# Edzzanine_Base.net
KiCad netlist of a schematic drawn in EAGLE
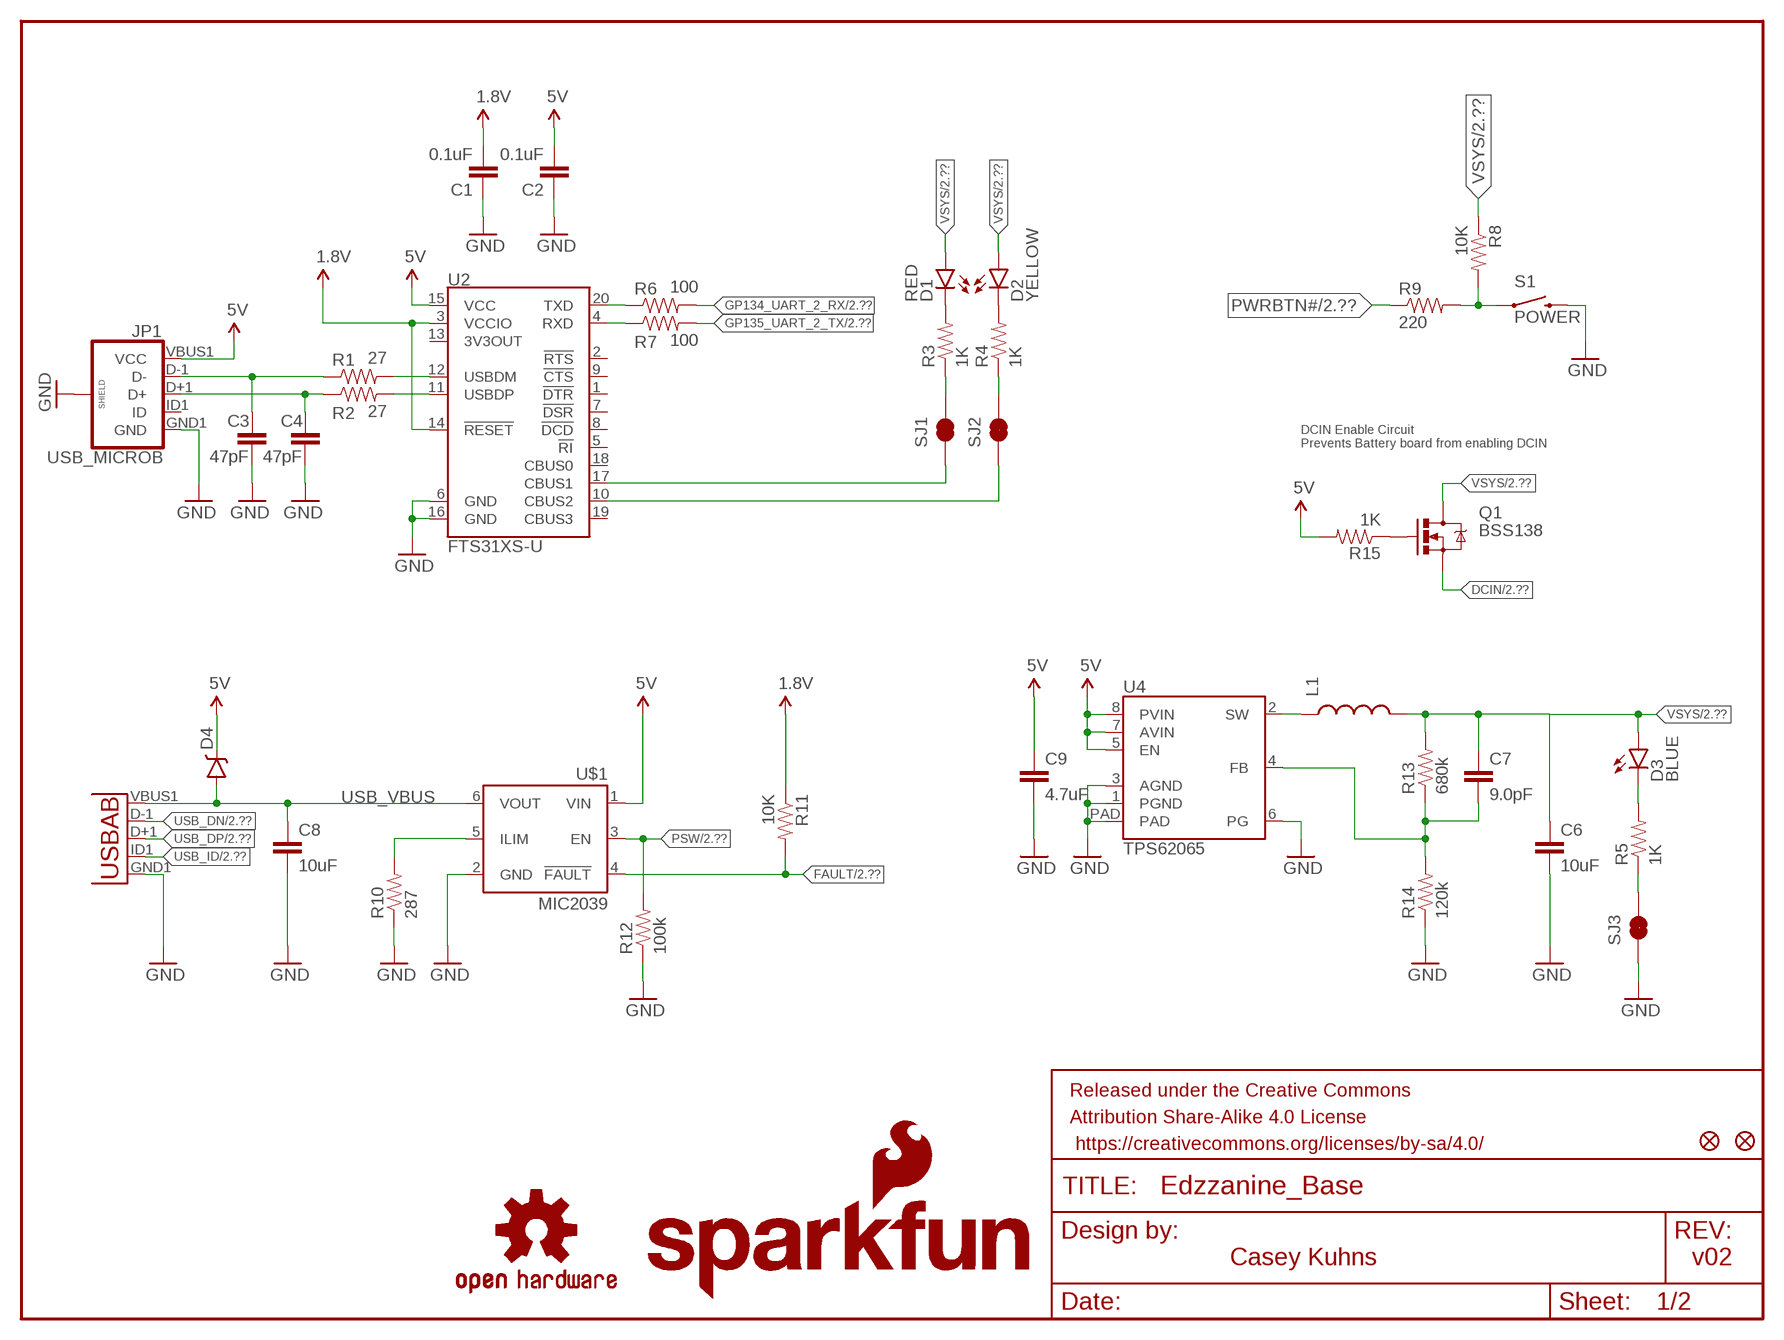
[diagram p0: schematic, sheet 1]
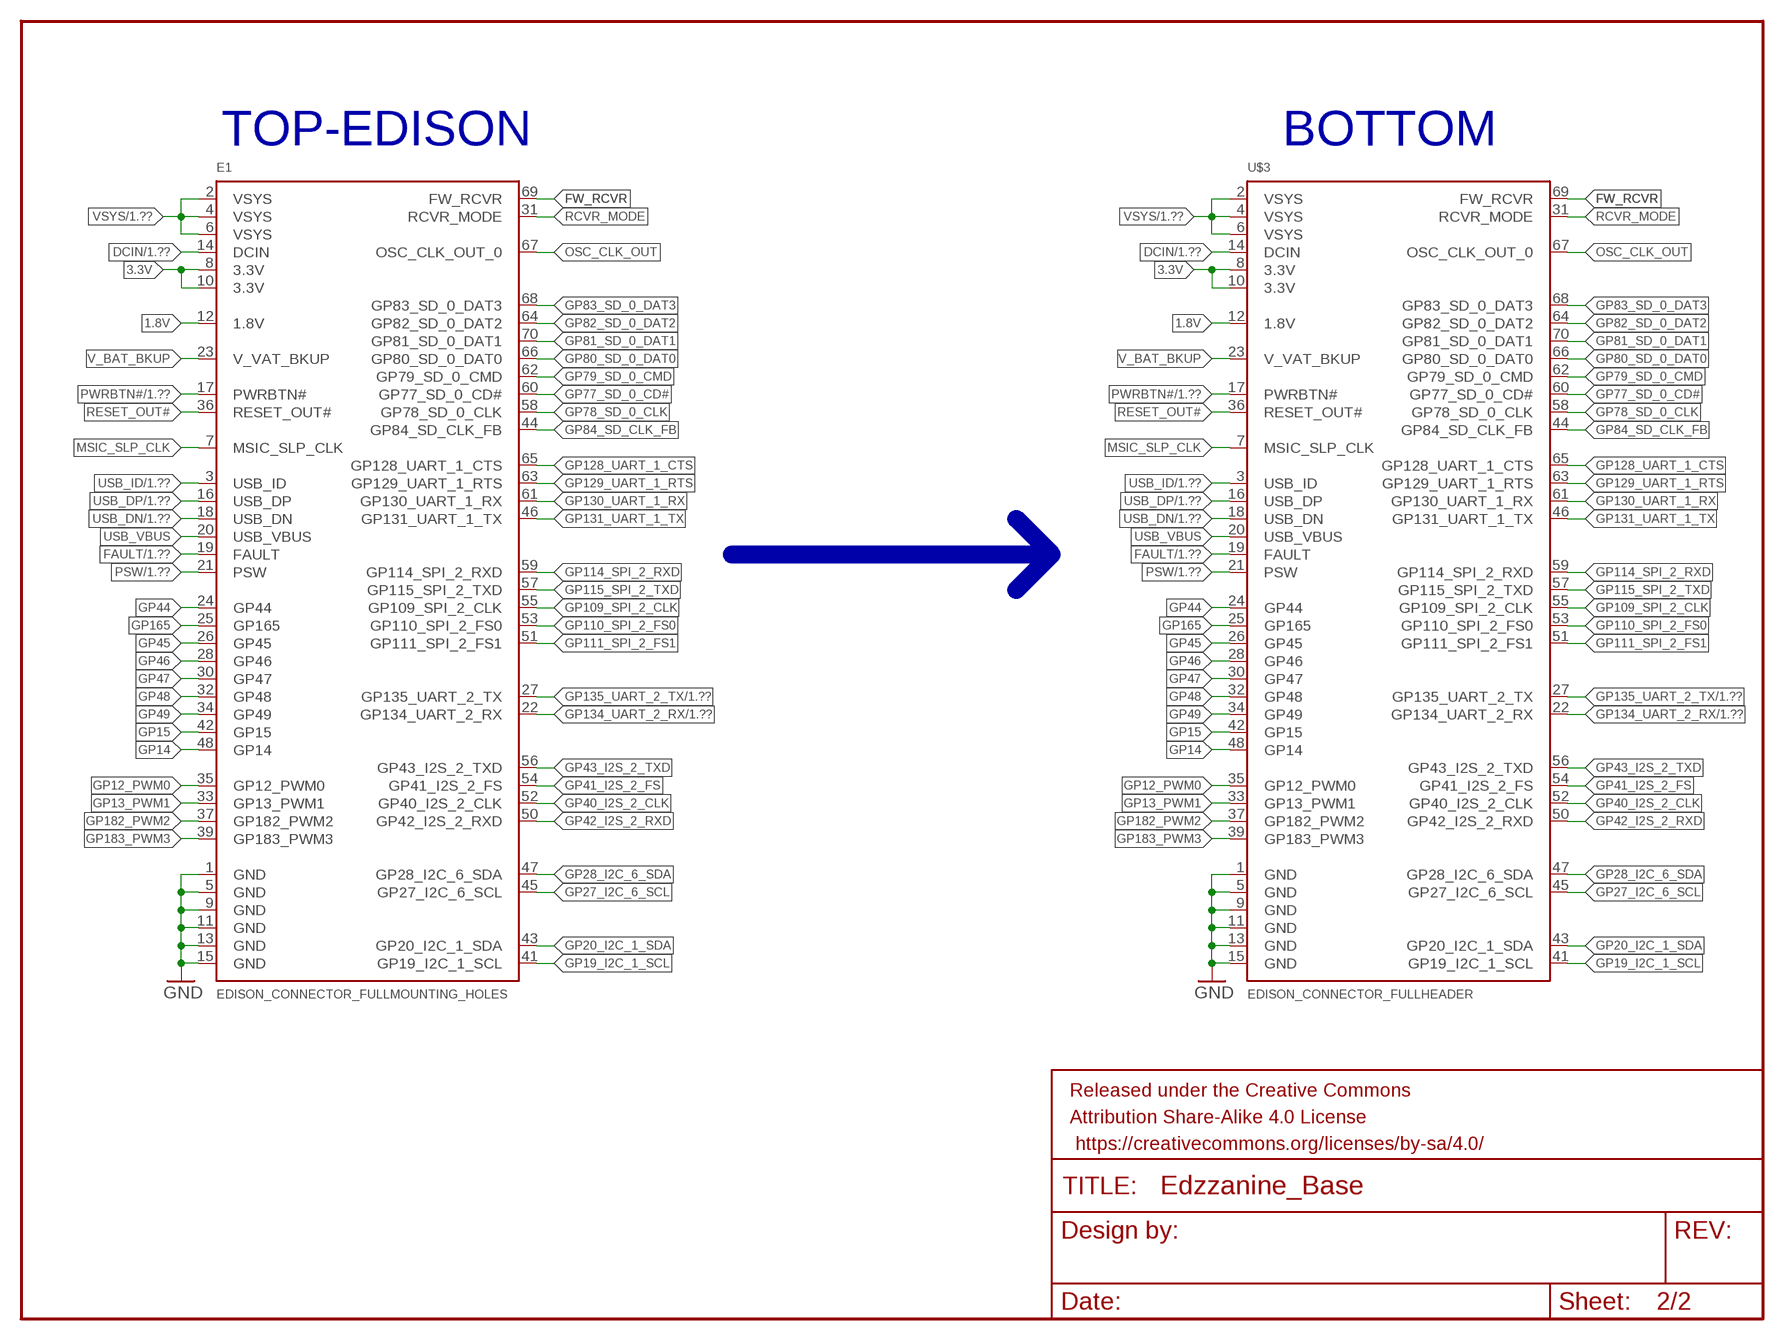
[diagram p1: schematic, sheet 2]

(export (version "E")
  (design (tool "Eeschema 10.0.6"))
  (components
    (comp (ref "C1")
      (value "0.1uF")
      (footprint "eagle-import:0603-CAP")
      (libsource (lib "eagle-import") (part "0.1UF-25V(+80/-20%)(0603)"))
    )
    (comp (ref "C2")
      (value "0.1uF")
      (footprint "eagle-import:0603-CAP")
      (libsource (lib "eagle-import") (part "0.1UF-25V(+80/-20%)(0603)"))
    )
    (comp (ref "C3")
      (value "47pF")
      (footprint "eagle-import:0603-CAP")
      (libsource (lib "eagle-import") (part "47PF-50V-5%(0603)"))
    )
    (comp (ref "C4")
      (value "47pF")
      (footprint "eagle-import:0603-CAP")
      (libsource (lib "eagle-import") (part "47PF-50V-5%(0603)"))
    )
    (comp (ref "C6")
      (value "10uF")
      (footprint "eagle-import:1206")
      (libsource (lib "eagle-import") (part "10UF-6.3V-20%(1206)"))
    )
    (comp (ref "C7")
      (value "9.0pF")
      (footprint "eagle-import:0603-CAP")
      (libsource (lib "eagle-import") (part "9.0PF-50V-10%(0603)"))
    )
    (comp (ref "C8")
      (value "10uF")
      (footprint "eagle-import:1206")
      (libsource (lib "eagle-import") (part "10UF-6.3V-20%(1206)"))
    )
    (comp (ref "C9")
      (value "4.7uF")
      (footprint "eagle-import:0603-CAP")
      (libsource (lib "eagle-import") (part "4.7UF-6.3V-10%(0603)0603"))
    )
    (comp (ref "D1")
      (value "RED")
      (footprint "eagle-import:LED-0603")
      (libsource (lib "eagle-import") (part "LED-RED0603"))
    )
    (comp (ref "D2")
      (value "YELLOW")
      (footprint "eagle-import:LED-0603")
      (libsource (lib "eagle-import") (part "LED-YELLOW0603"))
    )
    (comp (ref "D3")
      (value "BLUE")
      (footprint "eagle-import:LED-0603")
      (libsource (lib "eagle-import") (part "LED-BLUE0603"))
    )
    (comp (ref "D4")
      (value "DIODE-SCHOTTKY-MBRA140")
      (footprint "eagle-import:SMA-DIODE")
      (libsource (lib "eagle-import") (part "DIODE-SCHOTTKY-MBRA140"))
    )
    (comp (ref "FID1")
      (value "FIDUCIAL1X2")
      (footprint "eagle-import:FIDUCIAL-1X2")
      (libsource (lib "eagle-import") (part "FIDUCIAL1X2"))
    )
    (comp (ref "FID2")
      (value "FIDUCIAL1X2")
      (footprint "eagle-import:FIDUCIAL-1X2")
      (libsource (lib "eagle-import") (part "FIDUCIAL1X2"))
    )
    (comp (ref "FRAME1")
      (value "FRAME-LETTER")
      (footprint "eagle-import:CREATIVE_COMMONS")
      (libsource (lib "eagle-import") (part "FRAME-LETTER"))
    )
    (comp (ref "JP1")
      (value "USB_MICROB")
      (footprint "eagle-import:USB-B-MICRO-SMD_V03")
      (libsource (lib "eagle-import") (part "USB_MICROB_PLUGCONN-11752"))
    )
    (comp (ref "L1")
      (value "INDUCTOR")
      (footprint "eagle-import:INDUCTOR-SRP4020")
      (libsource (lib "eagle-import") (part "INDUCTOR"))
    )
    (comp (ref "LOGO1")
      (value "SFE_LOGO_NAME_FLAME.1_INCH")
      (footprint "eagle-import:SFE_LOGO_NAME_FLAME_.1")
      (libsource (lib "eagle-import") (part "SFE_LOGO_NAME_FLAME.1_INCH"))
    )
    (comp (ref "LOGO4")
      (value "OSHW-LOGOS")
      (footprint "eagle-import:OSHW-LOGO-S")
      (libsource (lib "eagle-import") (part "OSHW-LOGOS"))
    )
    (comp (ref "Q1")
      (value "BSS138")
      (footprint "eagle-import:SOT23-3")
      (libsource (lib "eagle-import") (part "MOSFET-NCHANNELBSS138"))
    )
    (comp (ref "R1")
      (value "27")
      (footprint "eagle-import:0603")
      (libsource (lib "eagle-import") (part "27OHM1/10W1%(0603)"))
    )
    (comp (ref "R2")
      (value "27")
      (footprint "eagle-import:0603")
      (libsource (lib "eagle-import") (part "27OHM1/10W1%(0603)"))
    )
    (comp (ref "R3")
      (value "1K")
      (footprint "eagle-import:0603-RES")
      (libsource (lib "eagle-import") (part "1KOHM1/10W1%(0603)"))
    )
    (comp (ref "R4")
      (value "1K")
      (footprint "eagle-import:0603-RES")
      (libsource (lib "eagle-import") (part "1KOHM1/10W1%(0603)"))
    )
    (comp (ref "R5")
      (value "1K")
      (footprint "eagle-import:0603-RES")
      (libsource (lib "eagle-import") (part "1KOHM1/10W1%(0603)"))
    )
    (comp (ref "R6")
      (value "100")
      (footprint "eagle-import:0603-RES")
      (libsource (lib "eagle-import") (part "100OHM1/10W1%(0603)"))
    )
    (comp (ref "R7")
      (value "100")
      (footprint "eagle-import:0603-RES")
      (libsource (lib "eagle-import") (part "100OHM1/10W1%(0603)"))
    )
    (comp (ref "R8")
      (value "10K")
      (footprint "eagle-import:0603-RES")
      (libsource (lib "eagle-import") (part "10KOHM1/10W1%(0603)0603"))
    )
    (comp (ref "R9")
      (value "220")
      (footprint "eagle-import:0603-RES")
      (libsource (lib "eagle-import") (part "22OHM1/10W1%(0603)"))
    )
    (comp (ref "R10")
      (value "287")
      (footprint "eagle-import:0603-RES")
      (libsource (lib "eagle-import") (part "287OHM-1/10W-1%(0603)"))
    )
    (comp (ref "R11")
      (value "10K")
      (footprint "eagle-import:0603-RES")
      (libsource (lib "eagle-import") (part "10KOHM1/10W1%(0603)0603"))
    )
    (comp (ref "R12")
      (value "100k")
      (footprint "eagle-import:0603-RES")
      (libsource (lib "eagle-import") (part "100KOHM1/10W1%(0603)"))
    )
    (comp (ref "R13")
      (value "680k")
      (footprint "eagle-import:0603-RES")
      (libsource (lib "eagle-import") (part "RESISTOR0603"))
    )
    (comp (ref "R14")
      (value "120k")
      (footprint "eagle-import:0603-RES")
      (libsource (lib "eagle-import") (part "RESISTOR0603"))
    )
    (comp (ref "R15")
      (value "1K")
      (footprint "eagle-import:0603-RES")
      (libsource (lib "eagle-import") (part "1KOHM1/10W1%(0603)"))
    )
    (comp (ref "S1")
      (value "POWER")
      (footprint "eagle-import:TACTILE_SWITCH-SMD-RIGHT-ANGLE")
      (libsource (lib "eagle-import") (part "SWITCH-MOMENTARY-2TACTILE-SWITCH-SMD-RIGHT-ANGLE"))
    )
    (comp (ref "SJ1")
      (value "JUMPER-PAD-2-NC_BY_TRACE")
      (footprint "eagle-import:PAD-JUMPER-2-NC_BY_TRACE_YES_SILK")
      (libsource (lib "eagle-import") (part "JUMPER-PAD-2-NC_BY_TRACE"))
    )
    (comp (ref "SJ2")
      (value "JUMPER-PAD-2-NC_BY_TRACE")
      (footprint "eagle-import:PAD-JUMPER-2-NC_BY_TRACE_YES_SILK")
      (libsource (lib "eagle-import") (part "JUMPER-PAD-2-NC_BY_TRACE"))
    )
    (comp (ref "SJ3")
      (value "JUMPER-PAD-2-NC_BY_TRACE")
      (footprint "eagle-import:PAD-JUMPER-2-NC_BY_TRACE_YES_SILK")
      (libsource (lib "eagle-import") (part "JUMPER-PAD-2-NC_BY_TRACE"))
    )
    (comp (ref "U$1")
      (value "MIC2039")
      (footprint "eagle-import:SOT23-6")
      (libsource (lib "eagle-import") (part "MIC2039"))
    )
    (comp (ref "U2")
      (value "FTS31XS-U")
      (footprint "eagle-import:SSOP20_L")
      (libsource (lib "eagle-import") (part "FT231XS"))
    )
    (comp (ref "U3")
      (value "USB-ABCONN-11794")
      (footprint "eagle-import:USB-AB-MICRO-SMD_V03")
      (libsource (lib "eagle-import") (part "USB-ABCONN-11794"))
    )
    (comp (ref "U4")
      (value "TPS62065")
      (footprint "eagle-import:WSON-8-PAD")
      (libsource (lib "eagle-import") (part "TPS62065"))
    )
    (comp (ref "E1")
      (value "EDISON_CONNECTOR_FULLMOUNTING_HOLES")
      (footprint "eagle-import:EDISON_DAUGHTER")
      (libsource (lib "eagle-import") (part "EDISON_CONNECTOR_FULLMOUNTING_HOLES"))
    )
    (comp (ref "FRAME2")
      (value "FRAME-LETTER")
      (footprint "eagle-import:CREATIVE_COMMONS")
      (libsource (lib "eagle-import") (part "FRAME-LETTER"))
    )
    (comp (ref "U$3")
      (value "EDISON_CONNECTOR_FULLHEADER")
      (footprint "eagle-import:DF40C-70DP-0.4(51)")
      (libsource (lib "eagle-import") (part "EDISON_CONNECTOR_FULLHEADER"))
    )
  )
  (nets
    (net (code "1") (name "1.8V") (class "Default")
      (node (ref "C1") (pin "2") (pinfunction "2_2") (pintype "passive"))
      (node (ref "E1") (pin "12") (pinfunction "1.8V_12") (pintype "bidirectional"))
      (node (ref "R11") (pin "1") (pinfunction "1_1") (pintype "passive"))
      (node (ref "U$3") (pin "12") (pinfunction "1.8V_12") (pintype "bidirectional"))
      (node (ref "U2") (pin "14") (pinfunction "~{RESET}_14") (pintype "bidirectional"))
      (node (ref "U2") (pin "3") (pinfunction "VCCIO_3") (pintype "bidirectional"))
    )
    (net (code "2") (name "3.3V") (class "Default")
      (node (ref "E1") (pin "10") (pinfunction "3.3V_10") (pintype "bidirectional"))
      (node (ref "E1") (pin "8") (pinfunction "3.3V_8") (pintype "bidirectional"))
      (node (ref "U$3") (pin "10") (pinfunction "3.3V_10") (pintype "bidirectional"))
      (node (ref "U$3") (pin "8") (pinfunction "3.3V_8") (pintype "bidirectional"))
    )
    (net (code "3") (name "5V") (class "Default")
      (node (ref "C2") (pin "2") (pinfunction "2_2") (pintype "passive"))
      (node (ref "C9") (pin "1") (pinfunction "1_1") (pintype "passive"))
      (node (ref "D4") (pin "C") (pinfunction "C_C") (pintype "passive"))
      (node (ref "JP1") (pin "VBUS1") (pinfunction "VCC_VBUS1") (pintype "bidirectional"))
      (node (ref "R15") (pin "2") (pinfunction "2_2") (pintype "passive"))
      (node (ref "U$1") (pin "1") (pinfunction "VIN_1") (pintype "bidirectional"))
      (node (ref "U2") (pin "15") (pinfunction "VCC_15") (pintype "bidirectional"))
      (node (ref "U4") (pin "5") (pinfunction "EN_5") (pintype "bidirectional"))
      (node (ref "U4") (pin "7") (pinfunction "AVIN_7") (pintype "bidirectional"))
      (node (ref "U4") (pin "8") (pinfunction "PVIN_8") (pintype "bidirectional"))
    )
    (net (code "4") (name "DCIN") (class "Default")
      (node (ref "E1") (pin "14") (pinfunction "DCIN_14") (pintype "bidirectional"))
      (node (ref "Q1") (pin "2") (pinfunction "S_2") (pintype "passive"))
      (node (ref "U$3") (pin "14") (pinfunction "DCIN_14") (pintype "bidirectional"))
    )
    (net (code "5") (name "FAULT") (class "Default")
      (node (ref "E1") (pin "19") (pinfunction "FAULT_19") (pintype "bidirectional"))
      (node (ref "R11") (pin "2") (pinfunction "2_2") (pintype "passive"))
      (node (ref "U$1") (pin "4") (pinfunction "~{FAULT}_4") (pintype "bidirectional"))
      (node (ref "U$3") (pin "19") (pinfunction "FAULT_19") (pintype "bidirectional"))
    )
    (net (code "6") (name "FW_RCVR") (class "Default")
      (node (ref "E1") (pin "69") (pinfunction "FW_RCVR_69") (pintype "bidirectional"))
      (node (ref "U$3") (pin "69") (pinfunction "FW_RCVR_69") (pintype "bidirectional"))
    )
    (net (code "7") (name "GND") (class "Default")
      (node (ref "C1") (pin "1") (pinfunction "1_1") (pintype "passive"))
      (node (ref "C2") (pin "1") (pinfunction "1_1") (pintype "passive"))
      (node (ref "C3") (pin "2") (pinfunction "2_2") (pintype "passive"))
      (node (ref "C4") (pin "2") (pinfunction "2_2") (pintype "passive"))
      (node (ref "C6") (pin "2") (pinfunction "2_2") (pintype "passive"))
      (node (ref "C8") (pin "2") (pinfunction "2_2") (pintype "passive"))
      (node (ref "C9") (pin "2") (pinfunction "2_2") (pintype "passive"))
      (node (ref "E1") (pin "1") (pinfunction "GND_1") (pintype "bidirectional"))
      (node (ref "E1") (pin "11") (pinfunction "GND_11") (pintype "bidirectional"))
      (node (ref "E1") (pin "13") (pinfunction "GND_13") (pintype "bidirectional"))
      (node (ref "E1") (pin "15") (pinfunction "GND_15") (pintype "bidirectional"))
      (node (ref "E1") (pin "5") (pinfunction "GND_5") (pintype "bidirectional"))
      (node (ref "E1") (pin "9") (pinfunction "GND_9") (pintype "bidirectional"))
      (node (ref "JP1") (pin "GND1") (pinfunction "GND_GND1") (pintype "bidirectional"))
      (node (ref "JP1") (pin "SHIELD1") (pinfunction "SHIELD_SHIELD1") (pintype "bidirectional"))
      (node (ref "JP1") (pin "SHIELD2") (pinfunction "SHIELD_SHIELD2") (pintype "bidirectional"))
      (node (ref "JP1") (pin "SHIELD3") (pinfunction "SHIELD_SHIELD3") (pintype "bidirectional"))
      (node (ref "R10") (pin "1") (pinfunction "1_1") (pintype "passive"))
      (node (ref "R12") (pin "1") (pinfunction "1_1") (pintype "passive"))
      (node (ref "R14") (pin "1") (pinfunction "1_1") (pintype "passive"))
      (node (ref "S1") (pin "2") (pinfunction "2_2") (pintype "passive"))
      (node (ref "SJ3") (pin "1") (pinfunction "1_1") (pintype "passive"))
      (node (ref "U$1") (pin "2") (pinfunction "GND_2") (pintype "bidirectional"))
      (node (ref "U$3") (pin "1") (pinfunction "GND_1") (pintype "bidirectional"))
      (node (ref "U$3") (pin "11") (pinfunction "GND_11") (pintype "bidirectional"))
      (node (ref "U$3") (pin "13") (pinfunction "GND_13") (pintype "bidirectional"))
      (node (ref "U$3") (pin "15") (pinfunction "GND_15") (pintype "bidirectional"))
      (node (ref "U$3") (pin "5") (pinfunction "GND_5") (pintype "bidirectional"))
      (node (ref "U$3") (pin "9") (pinfunction "GND_9") (pintype "bidirectional"))
      (node (ref "U2") (pin "16") (pinfunction "GND_16") (pintype "bidirectional"))
      (node (ref "U2") (pin "6") (pinfunction "GND_6") (pintype "bidirectional"))
      (node (ref "U3") (pin "GND1") (pinfunction "GND_GND1") (pintype "bidirectional"))
      (node (ref "U4") (pin "1") (pinfunction "PGND_1") (pintype "bidirectional"))
      (node (ref "U4") (pin "3") (pinfunction "AGND_3") (pintype "bidirectional"))
      (node (ref "U4") (pin "6") (pinfunction "PG_6") (pintype "bidirectional"))
      (node (ref "U4") (pin "PAD") (pinfunction "PAD_PAD") (pintype "bidirectional"))
    )
    (net (code "8") (name "GP12_PWM0") (class "Default")
      (node (ref "E1") (pin "35") (pinfunction "GP12_PWM0_35") (pintype "bidirectional"))
      (node (ref "U$3") (pin "35") (pinfunction "GP12_PWM0_35") (pintype "bidirectional"))
    )
    (net (code "9") (name "GP13_PWM1") (class "Default")
      (node (ref "E1") (pin "33") (pinfunction "GP13_PWM1_33") (pintype "bidirectional"))
      (node (ref "U$3") (pin "33") (pinfunction "GP13_PWM1_33") (pintype "bidirectional"))
    )
    (net (code "10") (name "GP14") (class "Default")
      (node (ref "E1") (pin "48") (pinfunction "GP14_48") (pintype "bidirectional"))
      (node (ref "U$3") (pin "48") (pinfunction "GP14_48") (pintype "bidirectional"))
    )
    (net (code "11") (name "GP15") (class "Default")
      (node (ref "E1") (pin "42") (pinfunction "GP15_42") (pintype "bidirectional"))
      (node (ref "U$3") (pin "42") (pinfunction "GP15_42") (pintype "bidirectional"))
    )
    (net (code "12") (name "GP19_I2C_1_SCL") (class "Default")
      (node (ref "E1") (pin "41") (pinfunction "GP19_I2C_1_SCL_41") (pintype "bidirectional"))
      (node (ref "U$3") (pin "41") (pinfunction "GP19_I2C_1_SCL_41") (pintype "bidirectional"))
    )
    (net (code "13") (name "GP20_I2C_1_SDA") (class "Default")
      (node (ref "E1") (pin "43") (pinfunction "GP20_I2C_1_SDA_43") (pintype "bidirectional"))
      (node (ref "U$3") (pin "43") (pinfunction "GP20_I2C_1_SDA_43") (pintype "bidirectional"))
    )
    (net (code "14") (name "GP27_I2C_6_SCL") (class "Default")
      (node (ref "E1") (pin "45") (pinfunction "GP27_I2C_6_SCL_45") (pintype "bidirectional"))
      (node (ref "U$3") (pin "45") (pinfunction "GP27_I2C_6_SCL_45") (pintype "bidirectional"))
    )
    (net (code "15") (name "GP28_I2C_6_SDA") (class "Default")
      (node (ref "E1") (pin "47") (pinfunction "GP28_I2C_6_SDA_47") (pintype "bidirectional"))
      (node (ref "U$3") (pin "47") (pinfunction "GP28_I2C_6_SDA_47") (pintype "bidirectional"))
    )
    (net (code "16") (name "GP40_I2S_2_CLK") (class "Default")
      (node (ref "E1") (pin "52") (pinfunction "GP40_I2S_2_CLK_52") (pintype "bidirectional"))
      (node (ref "U$3") (pin "52") (pinfunction "GP40_I2S_2_CLK_52") (pintype "bidirectional"))
    )
    (net (code "17") (name "GP41_I2S_2_FS") (class "Default")
      (node (ref "E1") (pin "54") (pinfunction "GP41_I2S_2_FS_54") (pintype "bidirectional"))
      (node (ref "U$3") (pin "54") (pinfunction "GP41_I2S_2_FS_54") (pintype "bidirectional"))
    )
    (net (code "18") (name "GP42_I2S_2_RXD") (class "Default")
      (node (ref "E1") (pin "50") (pinfunction "GP42_I2S_2_RXD_50") (pintype "bidirectional"))
      (node (ref "U$3") (pin "50") (pinfunction "GP42_I2S_2_RXD_50") (pintype "bidirectional"))
    )
    (net (code "19") (name "GP43_I2S_2_TXD") (class "Default")
      (node (ref "E1") (pin "56") (pinfunction "GP43_I2S_2_TXD_56") (pintype "bidirectional"))
      (node (ref "U$3") (pin "56") (pinfunction "GP43_I2S_2_TXD_56") (pintype "bidirectional"))
    )
    (net (code "20") (name "GP44") (class "Default")
      (node (ref "E1") (pin "24") (pinfunction "GP44_24") (pintype "bidirectional"))
      (node (ref "U$3") (pin "24") (pinfunction "GP44_24") (pintype "bidirectional"))
    )
    (net (code "21") (name "GP45") (class "Default")
      (node (ref "E1") (pin "26") (pinfunction "GP45_26") (pintype "bidirectional"))
      (node (ref "U$3") (pin "26") (pinfunction "GP45_26") (pintype "bidirectional"))
    )
    (net (code "22") (name "GP46") (class "Default")
      (node (ref "E1") (pin "28") (pinfunction "GP46_28") (pintype "bidirectional"))
      (node (ref "U$3") (pin "28") (pinfunction "GP46_28") (pintype "bidirectional"))
    )
    (net (code "23") (name "GP47") (class "Default")
      (node (ref "E1") (pin "30") (pinfunction "GP47_30") (pintype "bidirectional"))
      (node (ref "U$3") (pin "30") (pinfunction "GP47_30") (pintype "bidirectional"))
    )
    (net (code "24") (name "GP48") (class "Default")
      (node (ref "E1") (pin "32") (pinfunction "GP48_32") (pintype "bidirectional"))
      (node (ref "U$3") (pin "32") (pinfunction "GP48_32") (pintype "bidirectional"))
    )
    (net (code "25") (name "GP49") (class "Default")
      (node (ref "E1") (pin "34") (pinfunction "GP49_34") (pintype "bidirectional"))
      (node (ref "U$3") (pin "34") (pinfunction "GP49_34") (pintype "bidirectional"))
    )
    (net (code "26") (name "GP77_SD_0_CD#") (class "Default")
      (node (ref "E1") (pin "60") (pinfunction "GP77_SD_0_CD#_60") (pintype "bidirectional"))
      (node (ref "U$3") (pin "60") (pinfunction "GP77_SD_0_CD#_60") (pintype "bidirectional"))
    )
    (net (code "27") (name "GP78_SD_0_CLK") (class "Default")
      (node (ref "E1") (pin "58") (pinfunction "GP78_SD_0_CLK_58") (pintype "bidirectional"))
      (node (ref "U$3") (pin "58") (pinfunction "GP78_SD_0_CLK_58") (pintype "bidirectional"))
    )
    (net (code "28") (name "GP79_SD_0_CMD") (class "Default")
      (node (ref "E1") (pin "62") (pinfunction "GP79_SD_0_CMD_62") (pintype "bidirectional"))
      (node (ref "U$3") (pin "62") (pinfunction "GP79_SD_0_CMD_62") (pintype "bidirectional"))
    )
    (net (code "29") (name "GP80_SD_0_DAT0") (class "Default")
      (node (ref "E1") (pin "66") (pinfunction "GP80_SD_0_DAT0_66") (pintype "bidirectional"))
      (node (ref "U$3") (pin "66") (pinfunction "GP80_SD_0_DAT0_66") (pintype "bidirectional"))
    )
    (net (code "30") (name "GP81_SD_0_DAT1") (class "Default")
      (node (ref "E1") (pin "70") (pinfunction "GP81_SD_0_DAT1_70") (pintype "bidirectional"))
      (node (ref "U$3") (pin "70") (pinfunction "GP81_SD_0_DAT1_70") (pintype "bidirectional"))
    )
    (net (code "31") (name "GP82_SD_0_DAT2") (class "Default")
      (node (ref "E1") (pin "64") (pinfunction "GP82_SD_0_DAT2_64") (pintype "bidirectional"))
      (node (ref "U$3") (pin "64") (pinfunction "GP82_SD_0_DAT2_64") (pintype "bidirectional"))
    )
    (net (code "32") (name "GP83_SD_0_DAT3") (class "Default")
      (node (ref "E1") (pin "68") (pinfunction "GP83_SD_0_DAT3_68") (pintype "bidirectional"))
      (node (ref "U$3") (pin "68") (pinfunction "GP83_SD_0_DAT3_68") (pintype "bidirectional"))
    )
    (net (code "33") (name "GP84_SD_CLK_FB") (class "Default")
      (node (ref "E1") (pin "44") (pinfunction "GP84_SD_CLK_FB_44") (pintype "bidirectional"))
      (node (ref "U$3") (pin "44") (pinfunction "GP84_SD_CLK_FB_44") (pintype "bidirectional"))
    )
    (net (code "34") (name "GP109_SPI_2_CLK") (class "Default")
      (node (ref "E1") (pin "55") (pinfunction "GP109_SPI_2_CLK_55") (pintype "bidirectional"))
      (node (ref "U$3") (pin "55") (pinfunction "GP109_SPI_2_CLK_55") (pintype "bidirectional"))
    )
    (net (code "35") (name "GP110_SPI_2_FS0") (class "Default")
      (node (ref "E1") (pin "53") (pinfunction "GP110_SPI_2_FS0_53") (pintype "bidirectional"))
      (node (ref "U$3") (pin "53") (pinfunction "GP110_SPI_2_FS0_53") (pintype "bidirectional"))
    )
    (net (code "36") (name "GP111_SPI_2_FS1") (class "Default")
      (node (ref "E1") (pin "51") (pinfunction "GP111_SPI_2_FS1_51") (pintype "bidirectional"))
      (node (ref "U$3") (pin "51") (pinfunction "GP111_SPI_2_FS1_51") (pintype "bidirectional"))
    )
    (net (code "37") (name "GP114_SPI_2_RXD") (class "Default")
      (node (ref "E1") (pin "59") (pinfunction "GP114_SPI_2_RXD_59") (pintype "bidirectional"))
      (node (ref "U$3") (pin "59") (pinfunction "GP114_SPI_2_RXD_59") (pintype "bidirectional"))
    )
    (net (code "38") (name "GP115_SPI_2_TXD") (class "Default")
      (node (ref "E1") (pin "57") (pinfunction "GP115_SPI_2_TXD_57") (pintype "bidirectional"))
      (node (ref "U$3") (pin "57") (pinfunction "GP115_SPI_2_TXD_57") (pintype "bidirectional"))
    )
    (net (code "39") (name "GP128_UART_1_CTS") (class "Default")
      (node (ref "E1") (pin "65") (pinfunction "GP128_UART_1_CTS_65") (pintype "bidirectional"))
      (node (ref "U$3") (pin "65") (pinfunction "GP128_UART_1_CTS_65") (pintype "bidirectional"))
    )
    (net (code "40") (name "GP129_UART_1_RTS") (class "Default")
      (node (ref "E1") (pin "63") (pinfunction "GP129_UART_1_RTS_63") (pintype "bidirectional"))
      (node (ref "U$3") (pin "63") (pinfunction "GP129_UART_1_RTS_63") (pintype "bidirectional"))
    )
    (net (code "41") (name "GP130_UART_1_RX") (class "Default")
      (node (ref "E1") (pin "61") (pinfunction "GP130_UART_1_RX_61") (pintype "bidirectional"))
      (node (ref "U$3") (pin "61") (pinfunction "GP130_UART_1_RX_61") (pintype "bidirectional"))
    )
    (net (code "42") (name "GP131_UART_1_TX") (class "Default")
      (node (ref "E1") (pin "46") (pinfunction "GP131_UART_1_TX_46") (pintype "bidirectional"))
      (node (ref "U$3") (pin "46") (pinfunction "GP131_UART_1_TX_46") (pintype "bidirectional"))
    )
    (net (code "43") (name "GP134_UART_2_RX") (class "Default")
      (node (ref "E1") (pin "22") (pinfunction "GP134_UART_2_RX_22") (pintype "bidirectional"))
      (node (ref "R6") (pin "2") (pinfunction "2_2") (pintype "passive"))
      (node (ref "U$3") (pin "22") (pinfunction "GP134_UART_2_RX_22") (pintype "bidirectional"))
    )
    (net (code "44") (name "GP135_UART_2_TX") (class "Default")
      (node (ref "E1") (pin "27") (pinfunction "GP135_UART_2_TX_27") (pintype "bidirectional"))
      (node (ref "R7") (pin "2") (pinfunction "2_2") (pintype "passive"))
      (node (ref "U$3") (pin "27") (pinfunction "GP135_UART_2_TX_27") (pintype "bidirectional"))
    )
    (net (code "45") (name "GP165") (class "Default")
      (node (ref "E1") (pin "25") (pinfunction "GP165_25") (pintype "bidirectional"))
      (node (ref "U$3") (pin "25") (pinfunction "GP165_25") (pintype "bidirectional"))
    )
    (net (code "46") (name "GP182_PWM2") (class "Default")
      (node (ref "E1") (pin "37") (pinfunction "GP182_PWM2_37") (pintype "bidirectional"))
      (node (ref "U$3") (pin "37") (pinfunction "GP182_PWM2_37") (pintype "bidirectional"))
    )
    (net (code "47") (name "GP183_PWM3") (class "Default")
      (node (ref "E1") (pin "39") (pinfunction "GP183_PWM3_39") (pintype "bidirectional"))
      (node (ref "U$3") (pin "39") (pinfunction "GP183_PWM3_39") (pintype "bidirectional"))
    )
    (net (code "48") (name "MSIC_SLP_CLK") (class "Default")
      (node (ref "E1") (pin "7") (pinfunction "MSIC_SLP_CLK_7") (pintype "bidirectional"))
      (node (ref "U$3") (pin "7") (pinfunction "MSIC_SLP_CLK_7") (pintype "bidirectional"))
    )
    (net (code "49") (name "Net-(D1-PadC)") (class "Default")
      (node (ref "D1") (pin "C") (pinfunction "C_C") (pintype "passive"))
      (node (ref "R3") (pin "2") (pinfunction "2_2") (pintype "passive"))
    )
    (net (code "50") (name "Net-(D2-PadC)") (class "Default")
      (node (ref "D2") (pin "C") (pinfunction "C_C") (pintype "passive"))
      (node (ref "R4") (pin "2") (pinfunction "2_2") (pintype "passive"))
    )
    (net (code "51") (name "Net-(D3-PadC)") (class "Default")
      (node (ref "D3") (pin "C") (pinfunction "C_C") (pintype "passive"))
      (node (ref "R5") (pin "2") (pinfunction "2_2") (pintype "passive"))
    )
    (net (code "52") (name "Net-(JP1-D+)") (class "Default")
      (node (ref "C4") (pin "1") (pinfunction "1_1") (pintype "passive"))
      (node (ref "JP1") (pin "D+1") (pinfunction "D+_D+1") (pintype "bidirectional"))
      (node (ref "R2") (pin "1") (pinfunction "1_1") (pintype "passive"))
    )
    (net (code "53") (name "Net-(JP1-D-)") (class "Default")
      (node (ref "C3") (pin "1") (pinfunction "1_1") (pintype "passive"))
      (node (ref "JP1") (pin "D-1") (pinfunction "D-_D-1") (pintype "bidirectional"))
      (node (ref "R1") (pin "1") (pinfunction "1_1") (pintype "passive"))
    )
    (net (code "54") (name "Net-(L1-1)") (class "Default")
      (node (ref "L1") (pin "P$1") (pinfunction "1_P$1") (pintype "passive"))
      (node (ref "U4") (pin "2") (pinfunction "SW_2") (pintype "bidirectional"))
    )
    (net (code "55") (name "Net-(Q1-G)") (class "Default")
      (node (ref "Q1") (pin "1") (pinfunction "G_1") (pintype "passive"))
      (node (ref "R15") (pin "1") (pinfunction "1_1") (pintype "passive"))
    )
    (net (code "56") (name "Net-(R3-Pad1)") (class "Default")
      (node (ref "R3") (pin "1") (pinfunction "1_1") (pintype "passive"))
      (node (ref "SJ1") (pin "2") (pinfunction "2_2") (pintype "passive"))
    )
    (net (code "57") (name "Net-(R4-Pad1)") (class "Default")
      (node (ref "R4") (pin "1") (pinfunction "1_1") (pintype "passive"))
      (node (ref "SJ2") (pin "2") (pinfunction "2_2") (pintype "passive"))
    )
    (net (code "58") (name "Net-(R5-Pad1)") (class "Default")
      (node (ref "R5") (pin "1") (pinfunction "1_1") (pintype "passive"))
      (node (ref "SJ3") (pin "2") (pinfunction "2_2") (pintype "passive"))
    )
    (net (code "59") (name "Net-(R8-Pad2)") (class "Default")
      (node (ref "R8") (pin "2") (pinfunction "2_2") (pintype "passive"))
      (node (ref "R9") (pin "2") (pinfunction "2_2") (pintype "passive"))
      (node (ref "S1") (pin "1") (pinfunction "1_1") (pintype "passive"))
    )
    (net (code "60") (name "Net-(U$1-ILIM)") (class "Default")
      (node (ref "R10") (pin "2") (pinfunction "2_2") (pintype "passive"))
      (node (ref "U$1") (pin "5") (pinfunction "ILIM_5") (pintype "bidirectional"))
    )
    (net (code "61") (name "Net-(U2-CBUS1)") (class "Default")
      (node (ref "SJ1") (pin "1") (pinfunction "1_1") (pintype "passive"))
      (node (ref "U2") (pin "17") (pinfunction "CBUS1_17") (pintype "bidirectional"))
    )
    (net (code "62") (name "Net-(U2-CBUS2)") (class "Default")
      (node (ref "SJ2") (pin "1") (pinfunction "1_1") (pintype "passive"))
      (node (ref "U2") (pin "10") (pinfunction "CBUS2_10") (pintype "bidirectional"))
    )
    (net (code "63") (name "Net-(U2-RXD)") (class "Default")
      (node (ref "R7") (pin "1") (pinfunction "1_1") (pintype "passive"))
      (node (ref "U2") (pin "4") (pinfunction "RXD_4") (pintype "bidirectional"))
    )
    (net (code "64") (name "Net-(U2-TXD)") (class "Default")
      (node (ref "R6") (pin "1") (pinfunction "1_1") (pintype "passive"))
      (node (ref "U2") (pin "20") (pinfunction "TXD_20") (pintype "bidirectional"))
    )
    (net (code "65") (name "Net-(U2-USBDM)") (class "Default")
      (node (ref "R1") (pin "2") (pinfunction "2_2") (pintype "passive"))
      (node (ref "U2") (pin "12") (pinfunction "USBDM_12") (pintype "bidirectional"))
    )
    (net (code "66") (name "Net-(U2-USBDP)") (class "Default")
      (node (ref "R2") (pin "2") (pinfunction "2_2") (pintype "passive"))
      (node (ref "U2") (pin "11") (pinfunction "USBDP_11") (pintype "bidirectional"))
    )
    (net (code "67") (name "Net-(U4-FB)") (class "Default")
      (node (ref "C7") (pin "2") (pinfunction "2_2") (pintype "passive"))
      (node (ref "R13") (pin "1") (pinfunction "1_1") (pintype "passive"))
      (node (ref "R14") (pin "2") (pinfunction "2_2") (pintype "passive"))
      (node (ref "U4") (pin "4") (pinfunction "FB_4") (pintype "bidirectional"))
    )
    (net (code "68") (name "OSC_CLK_OUT") (class "Default")
      (node (ref "E1") (pin "67") (pinfunction "OSC_CLK_OUT_0_67") (pintype "bidirectional"))
      (node (ref "U$3") (pin "67") (pinfunction "OSC_CLK_OUT_0_67") (pintype "bidirectional"))
    )
    (net (code "69") (name "PSW") (class "Default")
      (node (ref "E1") (pin "21") (pinfunction "PSW_21") (pintype "bidirectional"))
      (node (ref "R12") (pin "2") (pinfunction "2_2") (pintype "passive"))
      (node (ref "U$1") (pin "3") (pinfunction "EN_3") (pintype "bidirectional"))
      (node (ref "U$3") (pin "21") (pinfunction "PSW_21") (pintype "bidirectional"))
    )
    (net (code "70") (name "PWRBTN#") (class "Default")
      (node (ref "E1") (pin "17") (pinfunction "PWRBTN#_17") (pintype "bidirectional"))
      (node (ref "R9") (pin "1") (pinfunction "1_1") (pintype "passive"))
      (node (ref "U$3") (pin "17") (pinfunction "PWRBTN#_17") (pintype "bidirectional"))
    )
    (net (code "71") (name "RCVR_MODE") (class "Default")
      (node (ref "E1") (pin "31") (pinfunction "RCVR_MODE_31") (pintype "bidirectional"))
      (node (ref "U$3") (pin "31") (pinfunction "RCVR_MODE_31") (pintype "bidirectional"))
    )
    (net (code "72") (name "RESET_OUT#") (class "Default")
      (node (ref "E1") (pin "36") (pinfunction "RESET_OUT#_36") (pintype "bidirectional"))
      (node (ref "U$3") (pin "36") (pinfunction "RESET_OUT#_36") (pintype "bidirectional"))
    )
    (net (code "73") (name "USB_DN") (class "Default")
      (node (ref "E1") (pin "18") (pinfunction "USB_DN_18") (pintype "bidirectional"))
      (node (ref "U$3") (pin "18") (pinfunction "USB_DN_18") (pintype "bidirectional"))
      (node (ref "U3") (pin "D-1") (pinfunction "D-_D-1") (pintype "bidirectional"))
    )
    (net (code "74") (name "USB_DP") (class "Default")
      (node (ref "E1") (pin "16") (pinfunction "USB_DP_16") (pintype "bidirectional"))
      (node (ref "U$3") (pin "16") (pinfunction "USB_DP_16") (pintype "bidirectional"))
      (node (ref "U3") (pin "D+1") (pinfunction "D+_D+1") (pintype "bidirectional"))
    )
    (net (code "75") (name "USB_ID") (class "Default")
      (node (ref "E1") (pin "3") (pinfunction "USB_ID_3") (pintype "bidirectional"))
      (node (ref "U$3") (pin "3") (pinfunction "USB_ID_3") (pintype "bidirectional"))
      (node (ref "U3") (pin "ID1") (pinfunction "USBID_ID1") (pintype "bidirectional"))
    )
    (net (code "76") (name "USB_VBUS") (class "Default")
      (node (ref "C8") (pin "1") (pinfunction "1_1") (pintype "passive"))
      (node (ref "D4") (pin "A") (pinfunction "A_A") (pintype "passive"))
      (node (ref "E1") (pin "20") (pinfunction "USB_VBUS_20") (pintype "bidirectional"))
      (node (ref "U$1") (pin "6") (pinfunction "VOUT_6") (pintype "bidirectional"))
      (node (ref "U$3") (pin "20") (pinfunction "USB_VBUS_20") (pintype "bidirectional"))
      (node (ref "U3") (pin "VBUS1") (pinfunction "VBUS_VBUS1") (pintype "bidirectional"))
    )
    (net (code "77") (name "VSYS") (class "Default")
      (node (ref "C6") (pin "1") (pinfunction "1_1") (pintype "passive"))
      (node (ref "C7") (pin "1") (pinfunction "1_1") (pintype "passive"))
      (node (ref "D1") (pin "A") (pinfunction "A_A") (pintype "passive"))
      (node (ref "D2") (pin "A") (pinfunction "A_A") (pintype "passive"))
      (node (ref "D3") (pin "A") (pinfunction "A_A") (pintype "passive"))
      (node (ref "E1") (pin "2") (pinfunction "VSYS_2") (pintype "bidirectional"))
      (node (ref "E1") (pin "4") (pinfunction "VSYS_4") (pintype "bidirectional"))
      (node (ref "E1") (pin "6") (pinfunction "VSYS_6") (pintype "bidirectional"))
      (node (ref "L1") (pin "P$2") (pinfunction "2_P$2") (pintype "passive"))
      (node (ref "Q1") (pin "3") (pinfunction "D_3") (pintype "passive"))
      (node (ref "R13") (pin "2") (pinfunction "2_2") (pintype "passive"))
      (node (ref "R8") (pin "1") (pinfunction "1_1") (pintype "passive"))
      (node (ref "U$3") (pin "2") (pinfunction "VSYS_2") (pintype "bidirectional"))
      (node (ref "U$3") (pin "4") (pinfunction "VSYS_4") (pintype "bidirectional"))
      (node (ref "U$3") (pin "6") (pinfunction "VSYS_6") (pintype "bidirectional"))
    )
    (net (code "78") (name "V_BAT_BKUP") (class "Default")
      (node (ref "E1") (pin "23") (pinfunction "V_VAT_BKUP_23") (pintype "bidirectional"))
      (node (ref "U$3") (pin "23") (pinfunction "V_VAT_BKUP_23") (pintype "bidirectional"))
    )
    (net (code "79") (name "unconnected-(JP1-ID-PadID1)") (class "Default")
      (node (ref "JP1") (pin "ID1") (pinfunction "ID_ID1") (pintype "bidirectional"))
    )
    (net (code "80") (name "unconnected-(U2-3V3OUT-Pad13)") (class "Default")
      (node (ref "U2") (pin "13") (pinfunction "3V3OUT_13") (pintype "bidirectional"))
    )
    (net (code "81") (name "unconnected-(U2-CBUS0-Pad18)") (class "Default")
      (node (ref "U2") (pin "18") (pinfunction "CBUS0_18") (pintype "bidirectional"))
    )
    (net (code "82") (name "unconnected-(U2-CBUS3-Pad19)") (class "Default")
      (node (ref "U2") (pin "19") (pinfunction "CBUS3_19") (pintype "bidirectional"))
    )
    (net (code "83") (name "unconnected-(U2-~{CTS}-Pad9)") (class "Default")
      (node (ref "U2") (pin "9") (pinfunction "~{CTS}_9") (pintype "bidirectional"))
    )
    (net (code "84") (name "unconnected-(U2-~{DCD}-Pad8)") (class "Default")
      (node (ref "U2") (pin "8") (pinfunction "~{DCD}_8") (pintype "bidirectional"))
    )
    (net (code "85") (name "unconnected-(U2-~{DSR}-Pad7)") (class "Default")
      (node (ref "U2") (pin "7") (pinfunction "~{DSR}_7") (pintype "bidirectional"))
    )
    (net (code "86") (name "unconnected-(U2-~{DTR}-Pad1)") (class "Default")
      (node (ref "U2") (pin "1") (pinfunction "~{DTR}_1") (pintype "bidirectional"))
    )
    (net (code "87") (name "unconnected-(U2-~{RI}-Pad5)") (class "Default")
      (node (ref "U2") (pin "5") (pinfunction "~{RI}_5") (pintype "bidirectional"))
    )
    (net (code "88") (name "unconnected-(U2-~{RTS}-Pad2)") (class "Default")
      (node (ref "U2") (pin "2") (pinfunction "~{RTS}_2") (pintype "bidirectional"))
    )
  )
)
